# Power.net
KiCad netlist of a schematic drawn in Altium Designer
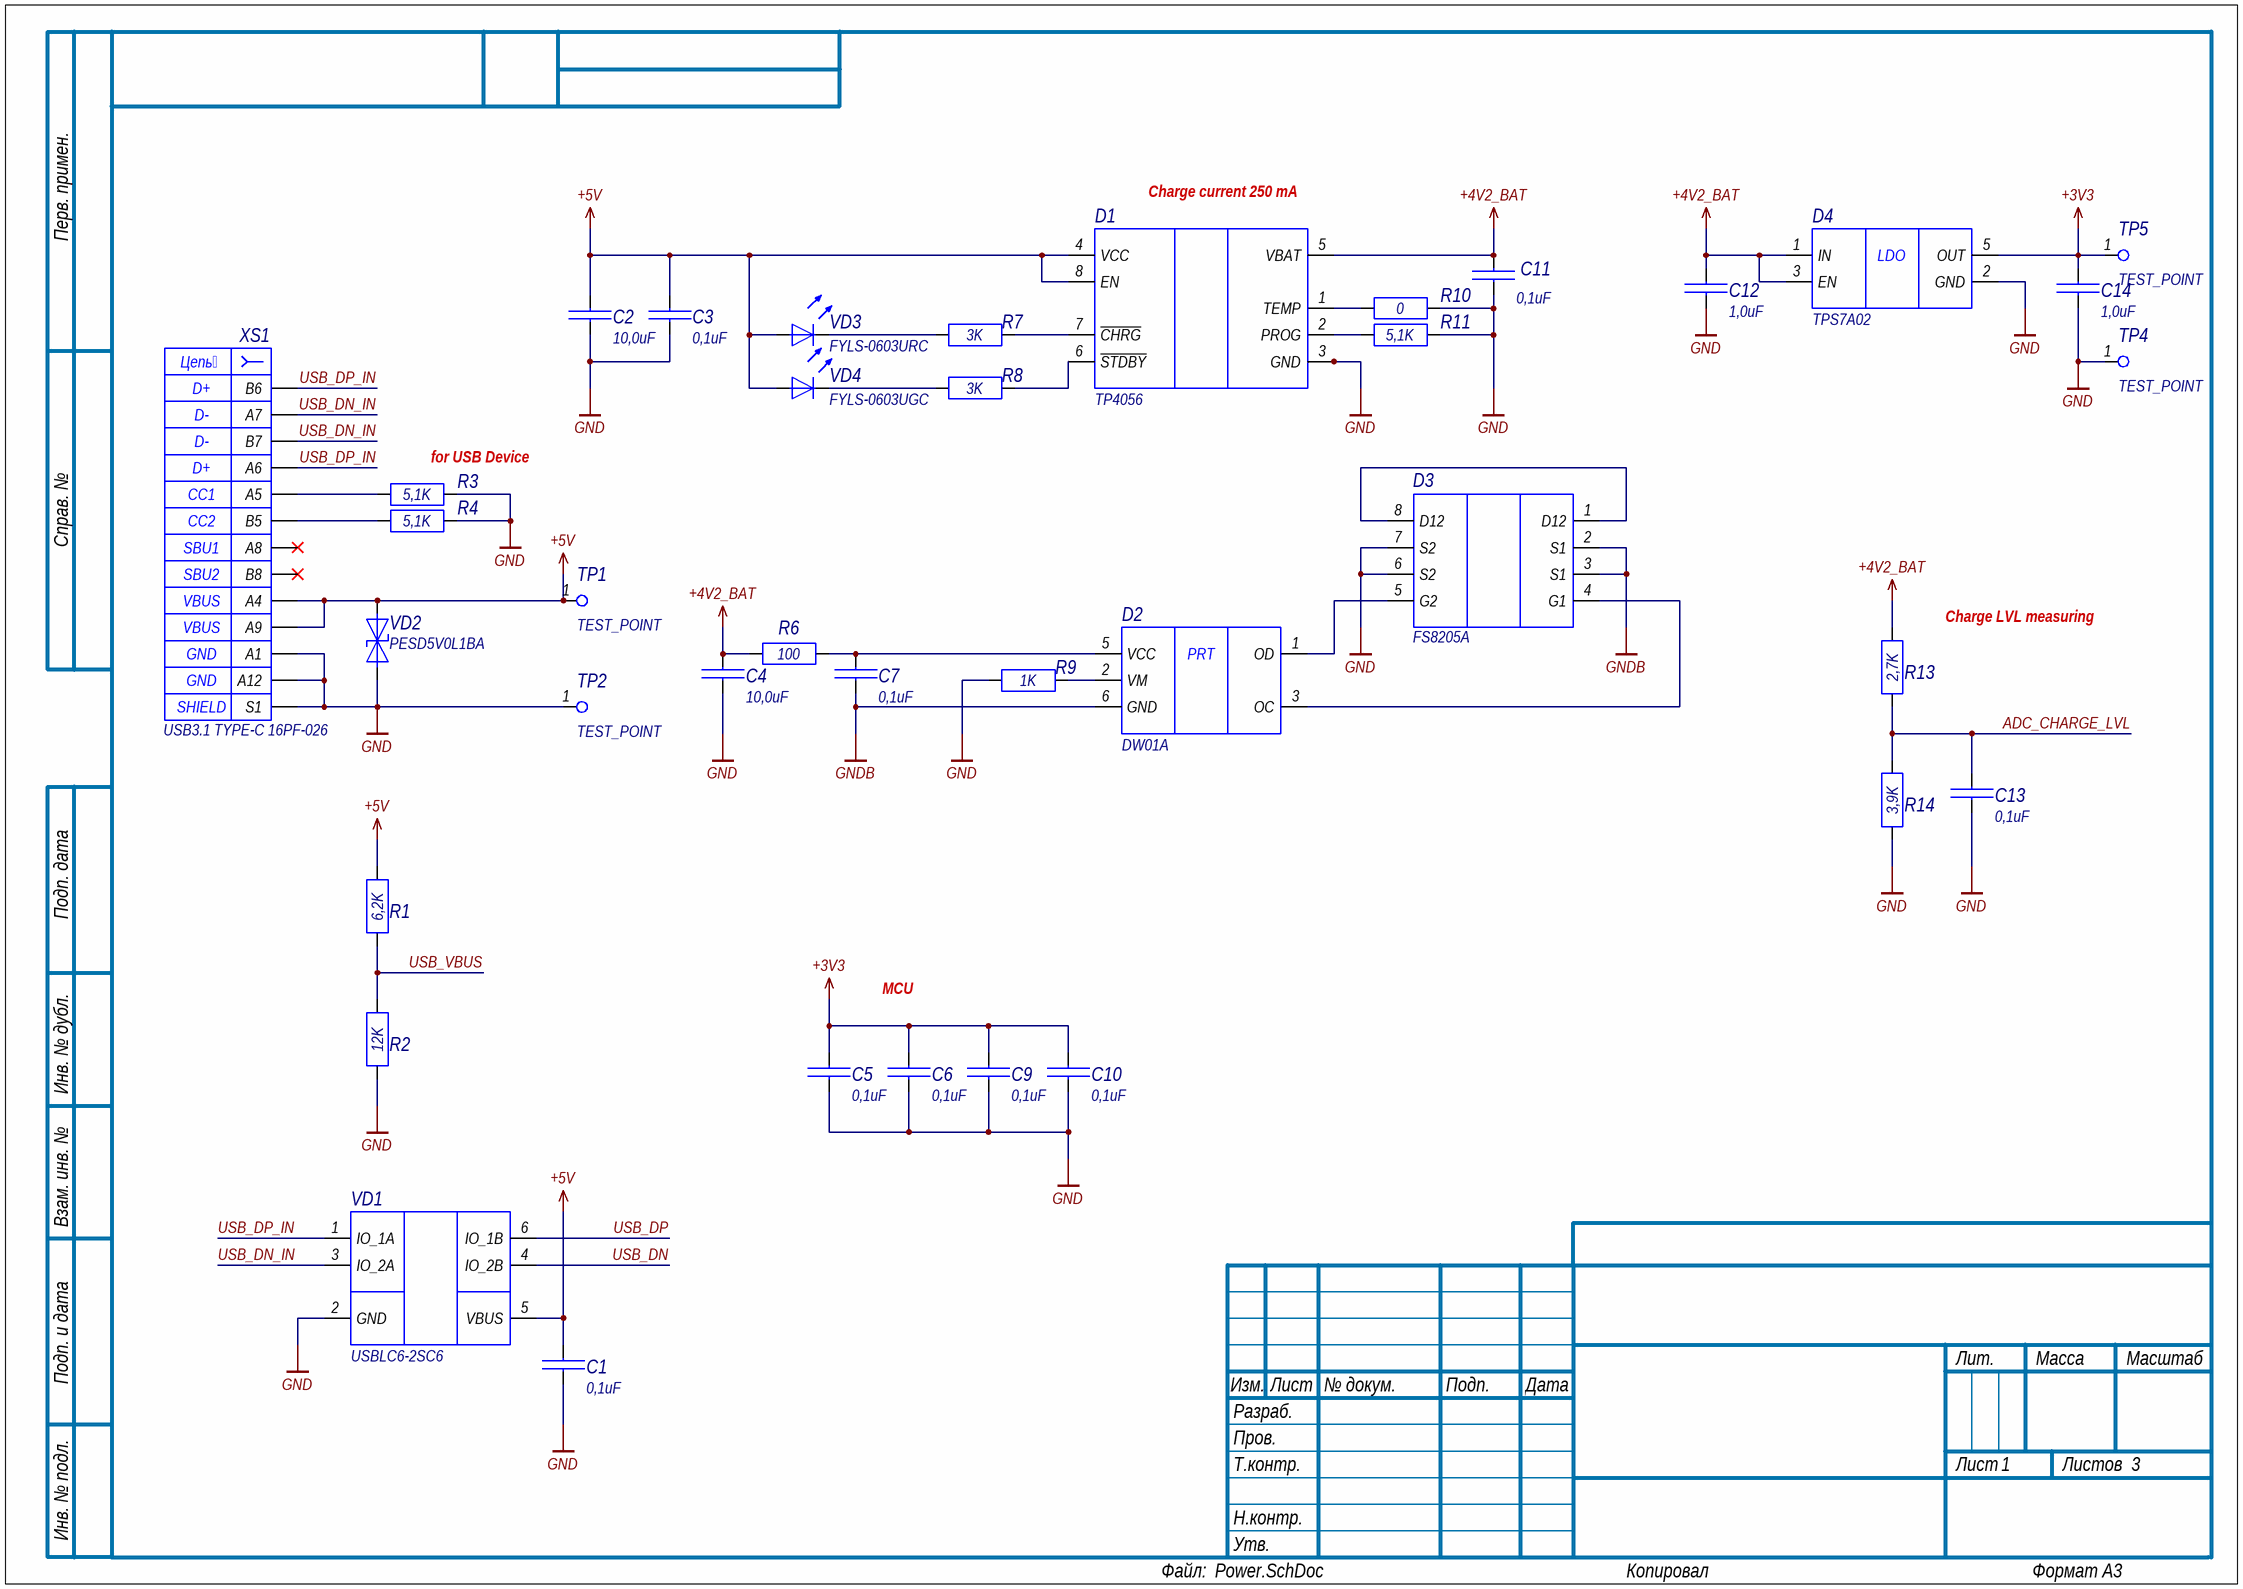
[diagram p0: Power.SchDoc]

(export (version "E")
  (design (tool "Eeschema 10.0.6"))
  (components
    (comp (ref "C1")
      (value "0,1uF")
      (footprint "CAP_0603")
      (description "Ceramic Capacitor SMD_0603 X7R")
      (fields (field (name "VOLTAGE") "25V") (field (name "PART NUMBER") "CAP_CER_0603_104_25_10_X7R"))
      (libsource (lib "myLib_ESKD") (part "CAPACITOR"))
    )
    (comp (ref "C2")
      (value "10,0uF")
      (footprint "CAP_0603")
      (description "Ceramic Capacitor SMD_0603 X5R")
      (fields (field (name "VOLTAGE") "25V") (field (name "PART NUMBER") "CAP_CER_0603_106_25_10_X5R"))
      (libsource (lib "myLib_ESKD") (part "CAPACITOR"))
    )
    (comp (ref "C3")
      (value "0,1uF")
      (footprint "CAP_0603")
      (description "Ceramic Capacitor SMD_0603 X7R")
      (fields (field (name "VOLTAGE") "25V") (field (name "PART NUMBER") "CAP_CER_0603_104_25_10_X7R"))
      (libsource (lib "myLib_ESKD") (part "CAPACITOR"))
    )
    (comp (ref "C4")
      (value "10,0uF")
      (footprint "CAP_0603")
      (description "Ceramic Capacitor SMD_0603 X5R")
      (fields (field (name "VOLTAGE") "10V") (field (name "PART NUMBER") "CAP_CER_0603_106_10_10_X5R"))
      (libsource (lib "myLib_ESKD") (part "CAPACITOR"))
    )
    (comp (ref "C5")
      (value "0,1uF")
      (footprint "CAP_0603")
      (description "Ceramic Capacitor SMD_0603 X7R")
      (fields (field (name "VOLTAGE") "25V") (field (name "PART NUMBER") "CAP_CER_0603_104_25_10_X7R"))
      (libsource (lib "myLib_ESKD") (part "CAPACITOR"))
    )
    (comp (ref "C6")
      (value "0,1uF")
      (footprint "CAP_0603")
      (description "Ceramic Capacitor SMD_0603 X7R")
      (fields (field (name "VOLTAGE") "25V") (field (name "PART NUMBER") "CAP_CER_0603_104_25_10_X7R"))
      (libsource (lib "myLib_ESKD") (part "CAPACITOR"))
    )
    (comp (ref "C7")
      (value "0,1uF")
      (footprint "CAP_0603")
      (description "Ceramic Capacitor SMD_0603 X7R")
      (fields (field (name "VOLTAGE") "25V") (field (name "PART NUMBER") "CAP_CER_0603_104_25_10_X7R"))
      (libsource (lib "myLib_ESKD") (part "CAPACITOR"))
    )
    (comp (ref "C9")
      (value "0,1uF")
      (footprint "CAP_0603")
      (description "Ceramic Capacitor SMD_0603 X7R")
      (fields (field (name "VOLTAGE") "25V") (field (name "PART NUMBER") "CAP_CER_0603_104_25_10_X7R"))
      (libsource (lib "myLib_ESKD") (part "CAPACITOR"))
    )
    (comp (ref "C10")
      (value "0,1uF")
      (footprint "CAP_0603")
      (description "Ceramic Capacitor SMD_0603 X7R")
      (fields (field (name "VOLTAGE") "25V") (field (name "PART NUMBER") "CAP_CER_0603_104_25_10_X7R"))
      (libsource (lib "myLib_ESKD") (part "CAPACITOR"))
    )
    (comp (ref "C11")
      (value "0,1uF")
      (footprint "CAP_0603")
      (description "Ceramic Capacitor SMD_0603 X7R")
      (fields (field (name "VOLTAGE") "25V") (field (name "PART NUMBER") "CAP_CER_0603_104_25_10_X7R"))
      (libsource (lib "myLib_ESKD") (part "CAPACITOR"))
    )
    (comp (ref "C12")
      (value "1,0uF")
      (footprint "CAP_0603")
      (description "Ceramic Capacitor SMD_0603 X5R")
      (fields (field (name "VOLTAGE") "25V") (field (name "PART NUMBER") "CAP_CER_0603_105_25_10_X5R"))
      (libsource (lib "myLib_ESKD") (part "CAPACITOR"))
    )
    (comp (ref "C13")
      (value "0,1uF")
      (footprint "CAP_0603")
      (description "Ceramic Capacitor SMD_0603 X7R")
      (fields (field (name "VOLTAGE") "25V") (field (name "PART NUMBER") "CAP_CER_0603_104_25_10_X7R"))
      (libsource (lib "myLib_ESKD") (part "CAPACITOR"))
    )
    (comp (ref "C14")
      (value "1,0uF")
      (footprint "CAP_0603")
      (description "Ceramic Capacitor SMD_0603 X5R")
      (fields (field (name "VOLTAGE") "25V") (field (name "PART NUMBER") "CAP_CER_0603_105_25_10_X5R"))
      (libsource (lib "myLib_ESKD") (part "CAPACITOR"))
    )
    (comp (ref "D1")
      (value "TP4056")
      (footprint "ESOP-8")
      (description "1A Standalone Linear Li-Ion Battery Charger")
      (fields (field (name "MANUFACTURER") "UMW"))
      (libsource (lib "myLib_ESKD") (part "TP4056"))
    )
    (comp (ref "D2") (value "DW01A") (footprint "SOT-23-6") (libsource (lib "myLib_ESKD") (part "DW01A")))
    (comp (ref "D3")
      (value "FS8205A")
      (footprint "TSSOP-8")
      (description "Dual N-Channel Enhancement Mode Power MOSFET")
      (fields (field (name "MANUFACTURER") "Tech Public"))
      (libsource (lib "myLib_ESKD") (part "FS8205A"))
    )
    (comp (ref "D4")
      (value "TPS7A02")
      (footprint "SOT-23-5")
      (description "TPS7A02 Nanopower IQ, 25-nA, 200-mA, Low-Dropout Voltage Regulator With Fast\nTransient Response")
      (fields
        (field (name "MANUFACTURER") "Texas Instruments")
        (field (name "MANUFACTURER PART NUMBER") "TPS7A0236PDBVR")
      )
      (libsource (lib "myLib_ESKD") (part "TPS7A02"))
    )
    (comp (ref "R1")
      (value "6,2K")
      (footprint "RES_0603")
      (description "Resistor fixed SMD_0603 5%")
      (fields (field (name "POWER") "100mW") (field (name "PART NUMBER") "RES_SMD_0603_6K2_5%"))
      (libsource (lib "myLib_ESKD") (part "RESISTOR"))
    )
    (comp (ref "R2")
      (value "12K")
      (footprint "RES_0603")
      (description "Resistor fixed SMD_0603 1%")
      (fields (field (name "POWER") "100mW") (field (name "PART NUMBER") "RES_SMD_0603_12K_1%"))
      (libsource (lib "myLib_ESKD") (part "RESISTOR"))
    )
    (comp (ref "R3")
      (value "5,1K")
      (footprint "RES_0603")
      (description "Resistor fixed SMD_0603 5%")
      (fields (field (name "POWER") "100mW") (field (name "PART NUMBER") "RES_SMD_0603_5K1_5%"))
      (libsource (lib "myLib_ESKD") (part "RESISTOR"))
    )
    (comp (ref "R4")
      (value "5,1K")
      (footprint "RES_0603")
      (description "Resistor fixed SMD_0603 5%")
      (fields (field (name "POWER") "100mW") (field (name "PART NUMBER") "RES_SMD_0603_5K1_5%"))
      (libsource (lib "myLib_ESKD") (part "RESISTOR"))
    )
    (comp (ref "R6")
      (value "100")
      (footprint "RES_0603")
      (description "Resistor fixed SMD_0603 5%")
      (fields (field (name "POWER") "100mW") (field (name "PART NUMBER") "RES_SMD_0603_100R_5%"))
      (libsource (lib "myLib_ESKD") (part "RESISTOR"))
    )
    (comp (ref "R7")
      (value "3K")
      (footprint "RES_0603")
      (description "Resistor fixed SMD_0603 5%")
      (fields (field (name "POWER") "100mW") (field (name "PART NUMBER") "RES_SMD_0603_3K_5%"))
      (libsource (lib "myLib_ESKD") (part "RESISTOR"))
    )
    (comp (ref "R8")
      (value "3K")
      (footprint "RES_0603")
      (description "Resistor fixed SMD_0603 5%")
      (fields (field (name "POWER") "100mW") (field (name "PART NUMBER") "RES_SMD_0603_3K_5%"))
      (libsource (lib "myLib_ESKD") (part "RESISTOR"))
    )
    (comp (ref "R9")
      (value "1K")
      (footprint "RES_0603")
      (description "Resistor fixed SMD_0603 5%")
      (fields (field (name "POWER") "100mW") (field (name "PART NUMBER") "RES_SMD_0603_1K_5%"))
      (libsource (lib "myLib_ESKD") (part "RESISTOR"))
    )
    (comp (ref "R10")
      (value "0")
      (footprint "RES_0603")
      (description "Resistor fixed SMD_0603 5%")
      (fields (field (name "POWER") "100mW") (field (name "PART NUMBER") "RES_SMD_0603_0R_5%"))
      (libsource (lib "myLib_ESKD") (part "RESISTOR"))
    )
    (comp (ref "R11")
      (value "5,1K")
      (footprint "RES_0603")
      (description "Resistor fixed SMD_0603 5%")
      (fields (field (name "POWER") "100mW") (field (name "PART NUMBER") "RES_SMD_0603_5K1_5%"))
      (libsource (lib "myLib_ESKD") (part "RESISTOR"))
    )
    (comp (ref "R13")
      (value "2,7K")
      (footprint "RES_0603")
      (description "Resistor fixed SMD_0603 5%")
      (fields (field (name "POWER") "100mW") (field (name "PART NUMBER") "RES_SMD_0603_2K7_5%"))
      (libsource (lib "myLib_ESKD") (part "RESISTOR"))
    )
    (comp (ref "R14")
      (value "3,9K")
      (footprint "RES_0603")
      (description "Resistor fixed SMD_0603 5%")
      (fields (field (name "POWER") "100mW") (field (name "PART NUMBER") "RES_SMD_0603_3K9_5%"))
      (libsource (lib "myLib_ESKD") (part "RESISTOR"))
    )
    (comp (ref "TP1")
      (value "TEST_POINT")
      (footprint "TP-SMD-R0.9x0.85")
      (description "Test Point, SMP Pad, 0.9x0.85mm")
      (fields (field (name "PART NUMBER") "TP-SMD-R0.9x0.85"))
      (libsource (lib "myLib_ESKD") (part "TEST_POINT"))
    )
    (comp (ref "TP2")
      (value "TEST_POINT")
      (footprint "TP-SMD-R0.9x0.85")
      (description "Test Point, SMP Pad, 0.9x0.85mm")
      (fields (field (name "PART NUMBER") "TP-SMD-R0.9x0.85"))
      (libsource (lib "myLib_ESKD") (part "TEST_POINT"))
    )
    (comp (ref "TP4")
      (value "TEST_POINT")
      (footprint "TP-SMD-R0.9x0.85")
      (description "Test Point, SMP Pad, 0.9x0.85mm")
      (fields (field (name "PART NUMBER") "TP-SMD-R0.9x0.85"))
      (libsource (lib "myLib_ESKD") (part "TEST_POINT"))
    )
    (comp (ref "TP5")
      (value "TEST_POINT")
      (footprint "TP-SMD-R0.9x0.85")
      (description "Test Point, SMP Pad, 0.9x0.85mm")
      (fields (field (name "PART NUMBER") "TP-SMD-R0.9x0.85"))
      (libsource (lib "myLib_ESKD") (part "TEST_POINT"))
    )
    (comp (ref "VD1")
      (value "USBLC6-2SC6")
      (footprint "SOT-23-6")
      (description "Low Capacitance 2-Line ESD Protection for USB Protection")
      (fields (field (name "VOLTAGE") "5V") (field (name "MANUFACTURER") "UMW"))
      (libsource (lib "myLib_ESKD") (part "USBLC6-2SC6"))
    )
    (comp (ref "VD2")
      (value "PESD5V0L1BA")
      (footprint "SOD-323F-NO-CATHODE")
      (description "Low Capacitance Bidirectional ESD Protection Diode")
      (fields (field (name "VOLTAGE") "5V") (field (name "MANUFACTURER") "UMW"))
      (libsource (lib "myLib_ESKD") (part "ZENER BIDIR"))
    )
    (comp (ref "VD3")
      (value "FYLS-0603URC")
      (footprint "LED_0603_R")
      (description "SMD 0603 LED Red")
      (fields (field (name "MANUFACTURER") "Foryard") (field (name "Comment") "LED"))
      (libsource (lib "myLib_ESKD") (part "LED"))
    )
    (comp (ref "VD4")
      (value "FYLS-0603UGC")
      (footprint "LED_0603_G")
      (description "SMD 0603 LED Green")
      (fields (field (name "MANUFACTURER") "Foryard") (field (name "Comment") "LED"))
      (libsource (lib "myLib_ESKD") (part "LED"))
    )
    (comp (ref "XS1")
      (value "USB3.1 TYPE-C 16PF-026")
      (footprint "USB3.1TYPE-C 16PF-26")
      (description "USB3.1 as USB2.0. Original: USB4110-GF_A")
      (fields
        (field (name "MANUFACTURER") "RUICHI")
        (field (name "MANUFACTURER PART NUMBER") "RUICHI USB3.1 TYPE-C")
      )
      (libsource (lib "myLib_ESKD") (part "USB3.1TYPE-C 16PF-26"))
    )
  )
  (nets
    (net (code "1") (name "+3V3") (class "Default")
      (node (ref "C10") (pin "1") (pinfunction "1_1") (pintype "passive"))
      (node (ref "C14") (pin "2") (pinfunction "2_2") (pintype "passive"))
      (node (ref "C5") (pin "1") (pinfunction "1_1") (pintype "passive"))
      (node (ref "C6") (pin "1") (pinfunction "1_1") (pintype "passive"))
      (node (ref "C9") (pin "1") (pinfunction "1_1") (pintype "passive"))
      (node (ref "D4") (pin "5") (pinfunction "OUT_5") (pintype "passive"))
      (node (ref "TP5") (pin "1") (pintype "passive"))
    )
    (net (code "2") (name "+4V2_BAT") (class "Default")
      (node (ref "C11") (pin "1") (pinfunction "1_1") (pintype "passive"))
      (node (ref "C12") (pin "2") (pinfunction "2_2") (pintype "passive"))
      (node (ref "C4") (pin "1") (pinfunction "1_1") (pintype "passive"))
      (node (ref "D1") (pin "5") (pinfunction "VBAT_5") (pintype "passive"))
      (node (ref "D4") (pin "1") (pinfunction "IN_1") (pintype "passive"))
      (node (ref "D4") (pin "3") (pinfunction "EN_3") (pintype "passive"))
      (node (ref "R13") (pin "2") (pinfunction "2_2") (pintype "passive"))
      (node (ref "R6") (pin "1") (pinfunction "1_1") (pintype "passive"))
    )
    (net (code "3") (name "+5V") (class "Default")
      (node (ref "C1") (pin "1") (pinfunction "1_1") (pintype "passive"))
      (node (ref "C2") (pin "1") (pinfunction "1_1") (pintype "passive"))
      (node (ref "C3") (pin "1") (pinfunction "1_1") (pintype "passive"))
      (node (ref "D1") (pin "4") (pinfunction "VCC_4") (pintype "passive"))
      (node (ref "D1") (pin "8") (pinfunction "EN_8") (pintype "passive"))
      (node (ref "R1") (pin "2") (pinfunction "2_2") (pintype "passive"))
      (node (ref "TP1") (pin "1") (pintype "passive"))
      (node (ref "VD1") (pin "5") (pinfunction "VBUS_5") (pintype "passive"))
      (node (ref "VD2") (pin "1") (pinfunction "1_1") (pintype "passive"))
      (node (ref "VD3") (pin "A") (pinfunction "A_A") (pintype "passive"))
      (node (ref "VD4") (pin "A") (pinfunction "A_A") (pintype "passive"))
      (node (ref "XS1") (pin "A4") (pinfunction "A4_A4") (pintype "passive"))
      (node (ref "XS1") (pin "A9") (pinfunction "A9_A9") (pintype "passive"))
    )
    (net (code "4") (name "/ADC_CHARGE_LVL") (class "Default")
      (node (ref "C13") (pin "1") (pinfunction "1_1") (pintype "passive"))
      (node (ref "R13") (pin "1") (pinfunction "1_1") (pintype "passive"))
      (node (ref "R14") (pin "2") (pinfunction "2_2") (pintype "passive"))
    )
    (net (code "5") (name "/USB_DN") (class "Default")
      (node (ref "VD1") (pin "4") (pinfunction "IO_2B_4") (pintype "passive"))
    )
    (net (code "6") (name "/USB_DN_IN") (class "Default")
      (node (ref "VD1") (pin "3") (pinfunction "IO_2A_3") (pintype "passive"))
      (node (ref "XS1") (pin "A7") (pinfunction "A7_A7") (pintype "passive"))
      (node (ref "XS1") (pin "B7") (pinfunction "B7_B7") (pintype "passive"))
    )
    (net (code "7") (name "/USB_DP") (class "Default")
      (node (ref "VD1") (pin "6") (pinfunction "IO_1B_6") (pintype "passive"))
    )
    (net (code "8") (name "/USB_DP_IN") (class "Default")
      (node (ref "VD1") (pin "1") (pinfunction "IO_1A_1") (pintype "passive"))
      (node (ref "XS1") (pin "A6") (pinfunction "A6_A6") (pintype "passive"))
      (node (ref "XS1") (pin "B6") (pinfunction "B6_B6") (pintype "passive"))
    )
    (net (code "9") (name "/USB_VBUS") (class "Default")
      (node (ref "R1") (pin "1") (pinfunction "1_1") (pintype "passive"))
      (node (ref "R2") (pin "2") (pinfunction "2_2") (pintype "passive"))
    )
    (net (code "10") (name "GND") (class "Default")
      (node (ref "C1") (pin "2") (pinfunction "2_2") (pintype "passive"))
      (node (ref "C10") (pin "2") (pinfunction "2_2") (pintype "passive"))
      (node (ref "C11") (pin "2") (pinfunction "2_2") (pintype "passive"))
      (node (ref "C12") (pin "1") (pinfunction "1_1") (pintype "passive"))
      (node (ref "C13") (pin "2") (pinfunction "2_2") (pintype "passive"))
      (node (ref "C14") (pin "1") (pinfunction "1_1") (pintype "passive"))
      (node (ref "C2") (pin "2") (pinfunction "2_2") (pintype "passive"))
      (node (ref "C3") (pin "2") (pinfunction "2_2") (pintype "passive"))
      (node (ref "C4") (pin "2") (pinfunction "2_2") (pintype "passive"))
      (node (ref "C5") (pin "2") (pinfunction "2_2") (pintype "passive"))
      (node (ref "C6") (pin "2") (pinfunction "2_2") (pintype "passive"))
      (node (ref "C9") (pin "2") (pinfunction "2_2") (pintype "passive"))
      (node (ref "D1") (pin "0") (pinfunction "EPAD_0") (pintype "passive"))
      (node (ref "D1") (pin "3") (pinfunction "GND_3") (pintype "passive"))
      (node (ref "D3") (pin "6") (pinfunction "S2_6") (pintype "passive"))
      (node (ref "D3") (pin "7") (pinfunction "S2_7") (pintype "passive"))
      (node (ref "D4") (pin "2") (pinfunction "GND_2") (pintype "passive"))
      (node (ref "R10") (pin "2") (pinfunction "2_2") (pintype "passive"))
      (node (ref "R11") (pin "2") (pinfunction "2_2") (pintype "passive"))
      (node (ref "R14") (pin "1") (pinfunction "1_1") (pintype "passive"))
      (node (ref "R2") (pin "1") (pinfunction "1_1") (pintype "passive"))
      (node (ref "R3") (pin "2") (pinfunction "2_2") (pintype "passive"))
      (node (ref "R4") (pin "2") (pinfunction "2_2") (pintype "passive"))
      (node (ref "R9") (pin "1") (pinfunction "1_1") (pintype "passive"))
      (node (ref "TP2") (pin "1") (pintype "passive"))
      (node (ref "TP4") (pin "1") (pintype "passive"))
      (node (ref "VD1") (pin "2") (pinfunction "GND_2") (pintype "passive"))
      (node (ref "VD2") (pin "2") (pinfunction "2_2") (pintype "passive"))
      (node (ref "XS1") (pin "A1") (pinfunction "A1_A1") (pintype "passive"))
      (node (ref "XS1") (pin "A12") (pinfunction "A12_A12") (pintype "passive"))
      (node (ref "XS1") (pin "S1") (pinfunction "S1_S1") (pintype "passive"))
    )
    (net (code "11") (name "GNDB") (class "Default")
      (node (ref "C7") (pin "2") (pinfunction "2_2") (pintype "passive"))
      (node (ref "D2") (pin "6") (pinfunction "GND_6") (pintype "passive"))
      (node (ref "D3") (pin "2") (pinfunction "S1_2") (pintype "passive"))
      (node (ref "D3") (pin "3") (pinfunction "S1_3") (pintype "passive"))
    )
    (net (code "12") (name "Net-(D1-PROG)") (class "Default")
      (node (ref "D1") (pin "2") (pinfunction "PROG_2") (pintype "passive"))
      (node (ref "R11") (pin "1") (pinfunction "1_1") (pintype "passive"))
    )
    (net (code "13") (name "Net-(D1-TEMP)") (class "Default")
      (node (ref "D1") (pin "1") (pinfunction "TEMP_1") (pintype "passive"))
      (node (ref "R10") (pin "1") (pinfunction "1_1") (pintype "passive"))
    )
    (net (code "14") (name "Net-(D1-~{CHRG})") (class "Default")
      (node (ref "D1") (pin "7") (pinfunction "~{CHRG}_7") (pintype "passive"))
      (node (ref "R7") (pin "2") (pinfunction "2_2") (pintype "passive"))
    )
    (net (code "15") (name "Net-(D1-~{STDBY})") (class "Default")
      (node (ref "D1") (pin "6") (pinfunction "~{STDBY}_6") (pintype "passive"))
      (node (ref "R8") (pin "2") (pinfunction "2_2") (pintype "passive"))
    )
    (net (code "16") (name "Net-(D2-OC)") (class "Default")
      (node (ref "D2") (pin "3") (pinfunction "OC_3") (pintype "passive"))
      (node (ref "D3") (pin "4") (pinfunction "G1_4") (pintype "passive"))
    )
    (net (code "17") (name "Net-(D2-OD)") (class "Default")
      (node (ref "D2") (pin "1") (pinfunction "OD_1") (pintype "passive"))
      (node (ref "D3") (pin "5") (pinfunction "G2_5") (pintype "passive"))
    )
    (net (code "18") (name "Net-(D2-VCC)") (class "Default")
      (node (ref "C7") (pin "1") (pinfunction "1_1") (pintype "passive"))
      (node (ref "D2") (pin "5") (pinfunction "VCC_5") (pintype "passive"))
      (node (ref "R6") (pin "2") (pinfunction "2_2") (pintype "passive"))
    )
    (net (code "19") (name "Net-(D2-VM)") (class "Default")
      (node (ref "D2") (pin "2") (pinfunction "VM_2") (pintype "passive"))
      (node (ref "R9") (pin "2") (pinfunction "2_2") (pintype "passive"))
    )
    (net (code "20") (name "Net-(D3-D12-Pad1)") (class "Default")
      (node (ref "D3") (pin "1") (pinfunction "D12_1") (pintype "passive"))
      (node (ref "D3") (pin "8") (pinfunction "D12_8") (pintype "passive"))
    )
    (net (code "21") (name "Net-(R3-Pad1)") (class "Default")
      (node (ref "R3") (pin "1") (pinfunction "1_1") (pintype "passive"))
      (node (ref "XS1") (pin "A5") (pinfunction "A5_A5") (pintype "passive"))
    )
    (net (code "22") (name "Net-(R4-Pad1)") (class "Default")
      (node (ref "R4") (pin "1") (pinfunction "1_1") (pintype "passive"))
      (node (ref "XS1") (pin "B5") (pinfunction "B5_B5") (pintype "passive"))
    )
    (net (code "23") (name "Net-(R7-Pad1)") (class "Default")
      (node (ref "R7") (pin "1") (pinfunction "1_1") (pintype "passive"))
      (node (ref "VD3") (pin "K") (pinfunction "K_K") (pintype "passive"))
    )
    (net (code "24") (name "Net-(R8-Pad1)") (class "Default")
      (node (ref "R8") (pin "1") (pinfunction "1_1") (pintype "passive"))
      (node (ref "VD4") (pin "K") (pinfunction "K_K") (pintype "passive"))
    )
    (net (code "25") (name "unconnected-(XS1-PadA8)") (class "Default")
      (node (ref "XS1") (pin "A8") (pinfunction "A8_A8") (pintype "passive+no_connect"))
    )
    (net (code "26") (name "unconnected-(XS1-PadB8)") (class "Default")
      (node (ref "XS1") (pin "B8") (pinfunction "B8_B8") (pintype "passive+no_connect"))
    )
  )
)
